# CC1101-E07-PI.net
KiCad netlist of a schematic drawn in EAGLE
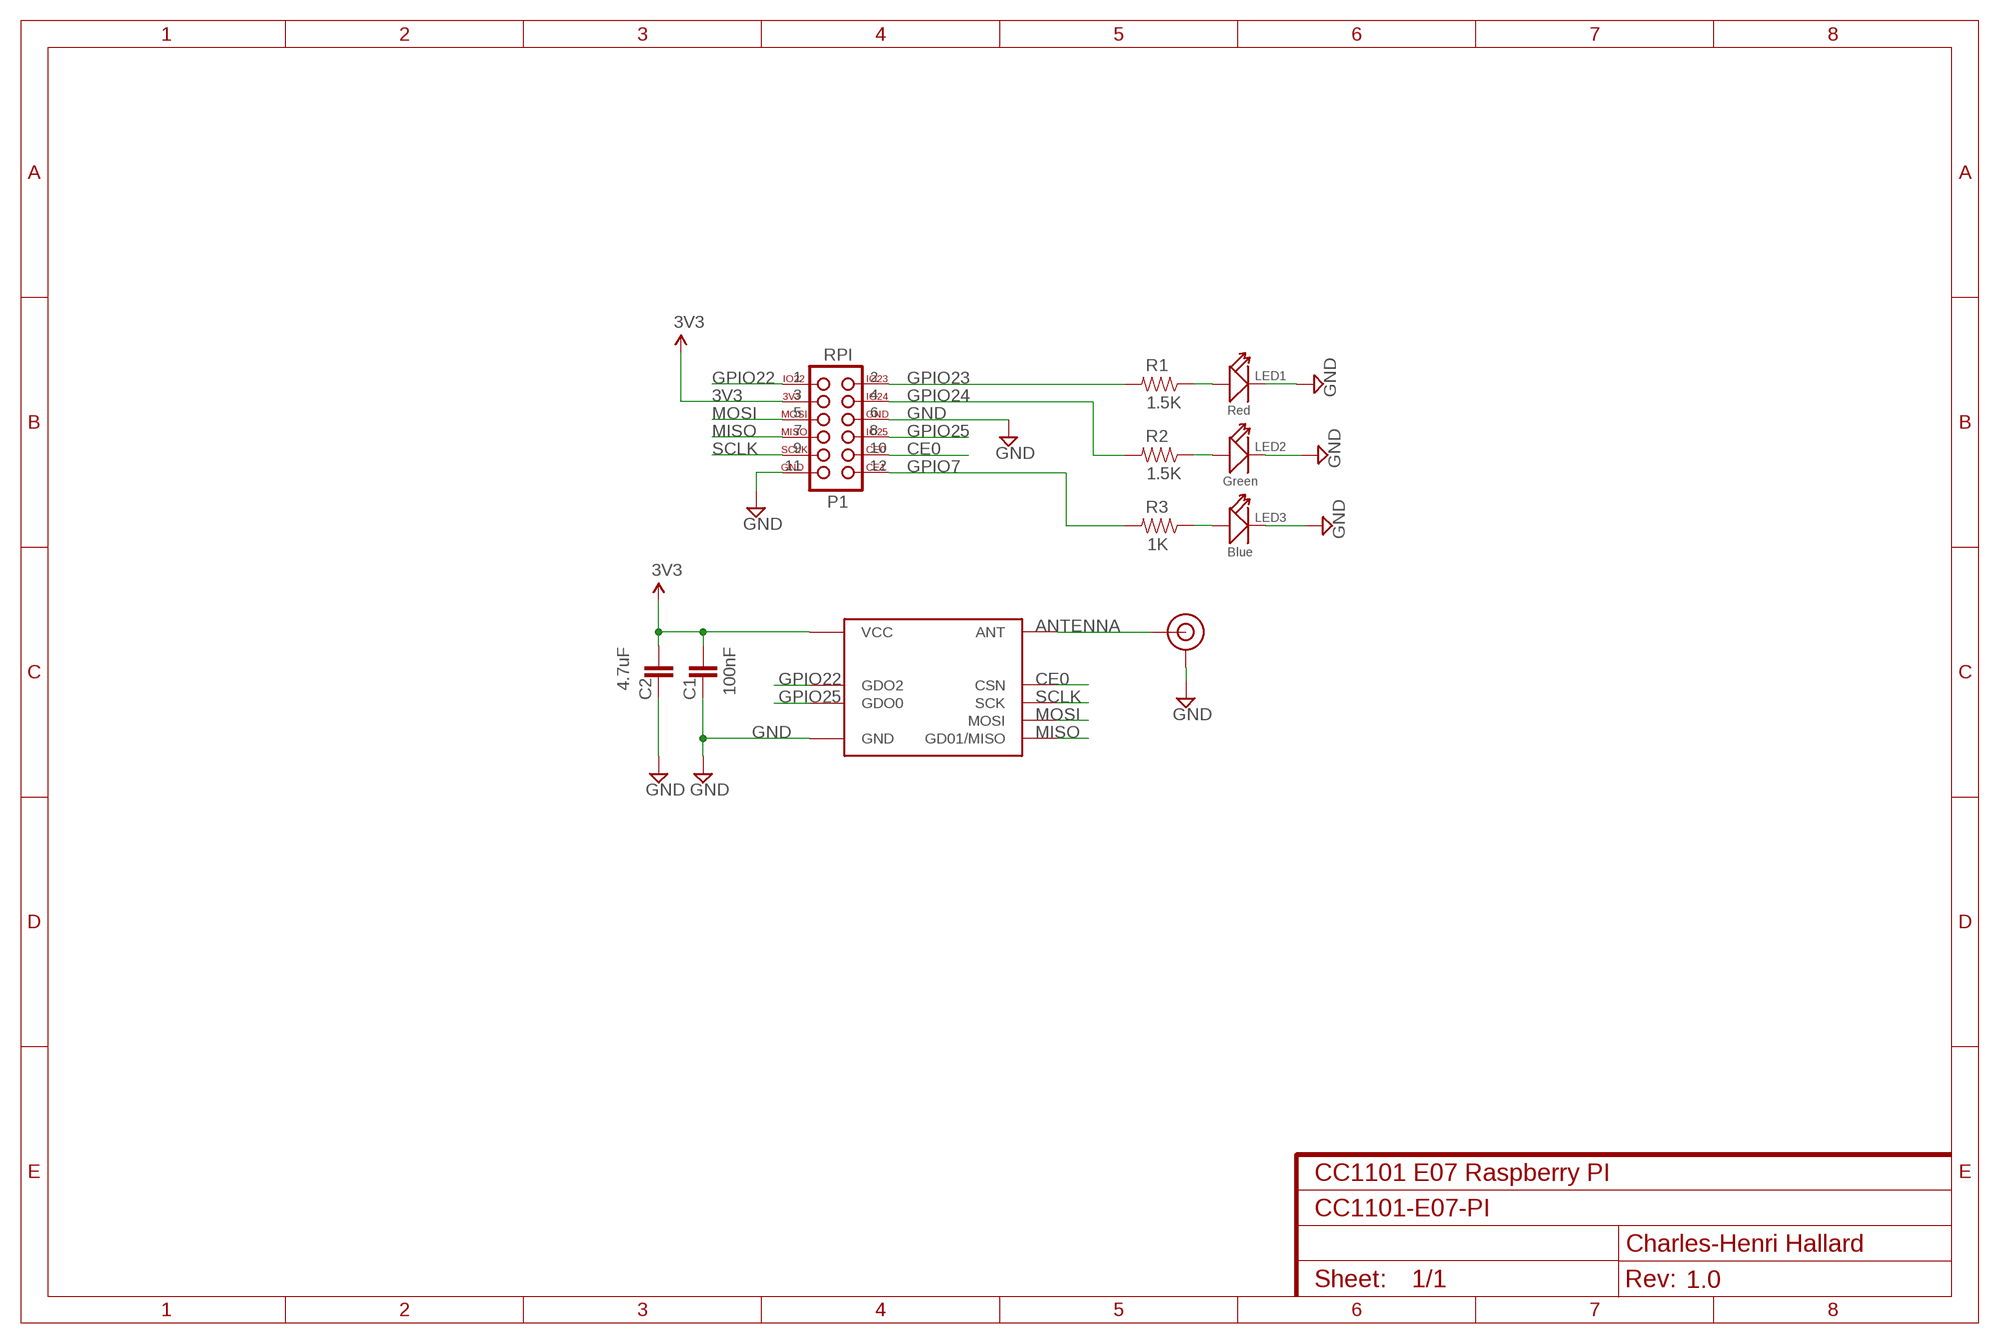
[diagram p0: schematic, sheet 1]

(export (version "E")
  (design (tool "Eeschema 10.0.6"))
  (components
    (comp (ref "C1")
      (value "100nF")
      (footprint "eagle-import:0402-CAP")
      (libsource (lib "eagle-import") (part "CAP0402-CAP"))
    )
    (comp (ref "C2")
      (value "4.7uF")
      (footprint "eagle-import:0402-CAP")
      (libsource (lib "eagle-import") (part "CAP0402-CAP"))
    )
    (comp (ref "J$1")
      (value "ANTENNASMA")
      (footprint "eagle-import:SMA_PAD")
      (libsource (lib "eagle-import") (part "ANTENNASMA"))
    )
    (comp (ref "J1")
      (value "2X6_BOTTOM")
      (footprint "eagle-import:2X06")
      (libsource (lib "eagle-import") (part "RASPBERRY_PI_2X6_BOTTOM"))
    )
    (comp (ref "LED1")
      (value "Red")
      (footprint "eagle-import:LED-0402")
      (fields (field (name "MPN") "BL-HB337A-AV-TRB"))
      (libsource (lib "eagle-import") (part "SMD-LED-CLEAR-BLUE(0402)"))
    )
    (comp (ref "LED2")
      (value "Green")
      (footprint "eagle-import:LED-0402")
      (fields (field (name "MPN") "BL-HB337A-AV-TRB"))
      (libsource (lib "eagle-import") (part "SMD-LED-CLEAR-BLUE(0402)"))
    )
    (comp (ref "LED3")
      (value "Blue")
      (footprint "eagle-import:LED-0402")
      (fields (field (name "MPN") "BL-HB337A-AV-TRB"))
      (libsource (lib "eagle-import") (part "SMD-LED-CLEAR-BLUE(0402)"))
    )
    (comp (ref "R1")
      (value "1.5K")
      (footprint "eagle-import:0402-RES")
      (libsource (lib "eagle-import") (part "RESISTOR0402-RES"))
    )
    (comp (ref "R2")
      (value "1.5K")
      (footprint "eagle-import:0402-RES")
      (libsource (lib "eagle-import") (part "RESISTOR0402-RES"))
    )
    (comp (ref "R3")
      (value "1K")
      (footprint "eagle-import:0402-RES")
      (libsource (lib "eagle-import") (part "RESISTOR0402-RES"))
    )
    (comp (ref "U1")
      (value "E07-400M10S")
      (footprint "eagle-import:E07-900M10S")
      (libsource (lib "eagle-import") (part "E07-900M10S"))
    )
  )
  (nets
    (net (code "1") (name "/ANTENNA") (class "Default")
      (node (ref "J$1") (pin "ANT0") (pinfunction "ANT_ANT0") (pintype "bidirectional"))
      (node (ref "J$1") (pin "ANT1") (pinfunction "ANT_ANT1") (pintype "bidirectional"))
      (node (ref "J$1") (pin "ANT2") (pinfunction "ANT_ANT2") (pintype "bidirectional"))
      (node (ref "U1") (pin "21") (pinfunction "ANT_21") (pintype "bidirectional"))
    )
    (net (code "2") (name "/CE0") (class "Default")
      (node (ref "J1") (pin "10") (pinfunction "24_10") (pintype "bidirectional"))
      (node (ref "U1") (pin "19") (pinfunction "CSN_19") (pintype "bidirectional"))
    )
    (net (code "3") (name "/GPIO7") (class "Default")
      (node (ref "J1") (pin "12") (pinfunction "26_12") (pintype "bidirectional"))
      (node (ref "R3") (pin "2") (pinfunction "2_2") (pintype "passive"))
    )
    (net (code "4") (name "/GPIO22") (class "Default")
      (node (ref "J1") (pin "1") (pinfunction "15_1") (pintype "bidirectional"))
      (node (ref "U1") (pin "14") (pinfunction "GDO2_14") (pintype "bidirectional"))
    )
    (net (code "5") (name "/GPIO23") (class "Default")
      (node (ref "J1") (pin "2") (pinfunction "16_2") (pintype "bidirectional"))
      (node (ref "R1") (pin "2") (pinfunction "2_2") (pintype "passive"))
    )
    (net (code "6") (name "/GPIO24") (class "Default")
      (node (ref "J1") (pin "4") (pinfunction "18_4") (pintype "bidirectional"))
      (node (ref "R2") (pin "2") (pinfunction "2_2") (pintype "passive"))
    )
    (net (code "7") (name "/GPIO25") (class "Default")
      (node (ref "J1") (pin "8") (pinfunction "22_8") (pintype "bidirectional"))
      (node (ref "U1") (pin "15") (pinfunction "GDO0_15") (pintype "bidirectional"))
    )
    (net (code "8") (name "/MISO") (class "Default")
      (node (ref "J1") (pin "7") (pinfunction "21_7") (pintype "bidirectional"))
      (node (ref "U1") (pin "16") (pinfunction "GD01/MISO_16") (pintype "bidirectional"))
    )
    (net (code "9") (name "/MOSI") (class "Default")
      (node (ref "J1") (pin "5") (pinfunction "19_5") (pintype "bidirectional"))
      (node (ref "U1") (pin "17") (pinfunction "MOSI_17") (pintype "bidirectional"))
    )
    (net (code "10") (name "/SCLK") (class "Default")
      (node (ref "J1") (pin "9") (pinfunction "23_9") (pintype "bidirectional"))
      (node (ref "U1") (pin "18") (pinfunction "SCK_18") (pintype "bidirectional"))
    )
    (net (code "11") (name "3V3") (class "Default")
      (node (ref "C1") (pin "2") (pinfunction "2_2") (pintype "passive"))
      (node (ref "C2") (pin "2") (pinfunction "2_2") (pintype "passive"))
      (node (ref "J1") (pin "3") (pinfunction "17_3") (pintype "power_in"))
      (node (ref "U1") (pin "9") (pinfunction "VCC_9") (pintype "bidirectional"))
    )
    (net (code "12") (name "GND") (class "Default")
      (node (ref "C1") (pin "1") (pinfunction "1_1") (pintype "passive"))
      (node (ref "C2") (pin "1") (pinfunction "1_1") (pintype "passive"))
      (node (ref "J$1") (pin "GND3") (pinfunction "GND_GND3") (pintype "bidirectional"))
      (node (ref "J$1") (pin "GND4") (pinfunction "GND_GND4") (pintype "bidirectional"))
      (node (ref "J$1") (pin "GND5") (pinfunction "GND_GND5") (pintype "bidirectional"))
      (node (ref "J$1") (pin "GND6") (pinfunction "GND_GND6") (pintype "bidirectional"))
      (node (ref "J1") (pin "11") (pinfunction "25_11") (pintype "passive"))
      (node (ref "J1") (pin "6") (pinfunction "20_6") (pintype "passive"))
      (node (ref "LED1") (pin "-") (pinfunction "-_-") (pintype "passive"))
      (node (ref "LED2") (pin "-") (pinfunction "-_-") (pintype "passive"))
      (node (ref "LED3") (pin "-") (pinfunction "-_-") (pintype "passive"))
      (node (ref "U1") (pin "1") (pinfunction "GND_1") (pintype "bidirectional"))
      (node (ref "U1") (pin "11") (pinfunction "GND_11") (pintype "bidirectional"))
      (node (ref "U1") (pin "12") (pinfunction "GND_12") (pintype "bidirectional"))
      (node (ref "U1") (pin "2") (pinfunction "GND_2") (pintype "bidirectional"))
      (node (ref "U1") (pin "20") (pinfunction "GND_20") (pintype "bidirectional"))
      (node (ref "U1") (pin "22") (pinfunction "GND_22") (pintype "bidirectional"))
      (node (ref "U1") (pin "3") (pinfunction "GND_3") (pintype "bidirectional"))
      (node (ref "U1") (pin "4") (pinfunction "GND_4") (pintype "bidirectional"))
      (node (ref "U1") (pin "5") (pinfunction "GND_5") (pintype "bidirectional"))
    )
    (net (code "13") (name "Net-(LED1-Pad+)") (class "Default")
      (node (ref "LED1") (pin "+") (pinfunction "+_+") (pintype "passive"))
      (node (ref "R1") (pin "1") (pinfunction "1_1") (pintype "passive"))
    )
    (net (code "14") (name "Net-(LED2-Pad+)") (class "Default")
      (node (ref "LED2") (pin "+") (pinfunction "+_+") (pintype "passive"))
      (node (ref "R2") (pin "1") (pinfunction "1_1") (pintype "passive"))
    )
    (net (code "15") (name "Net-(LED3-Pad+)") (class "Default")
      (node (ref "LED3") (pin "+") (pinfunction "+_+") (pintype "passive"))
      (node (ref "R3") (pin "1") (pinfunction "1_1") (pintype "passive"))
    )
  )
)
